# scheme.net
KiCad netlist of a schematic drawn in EAGLE
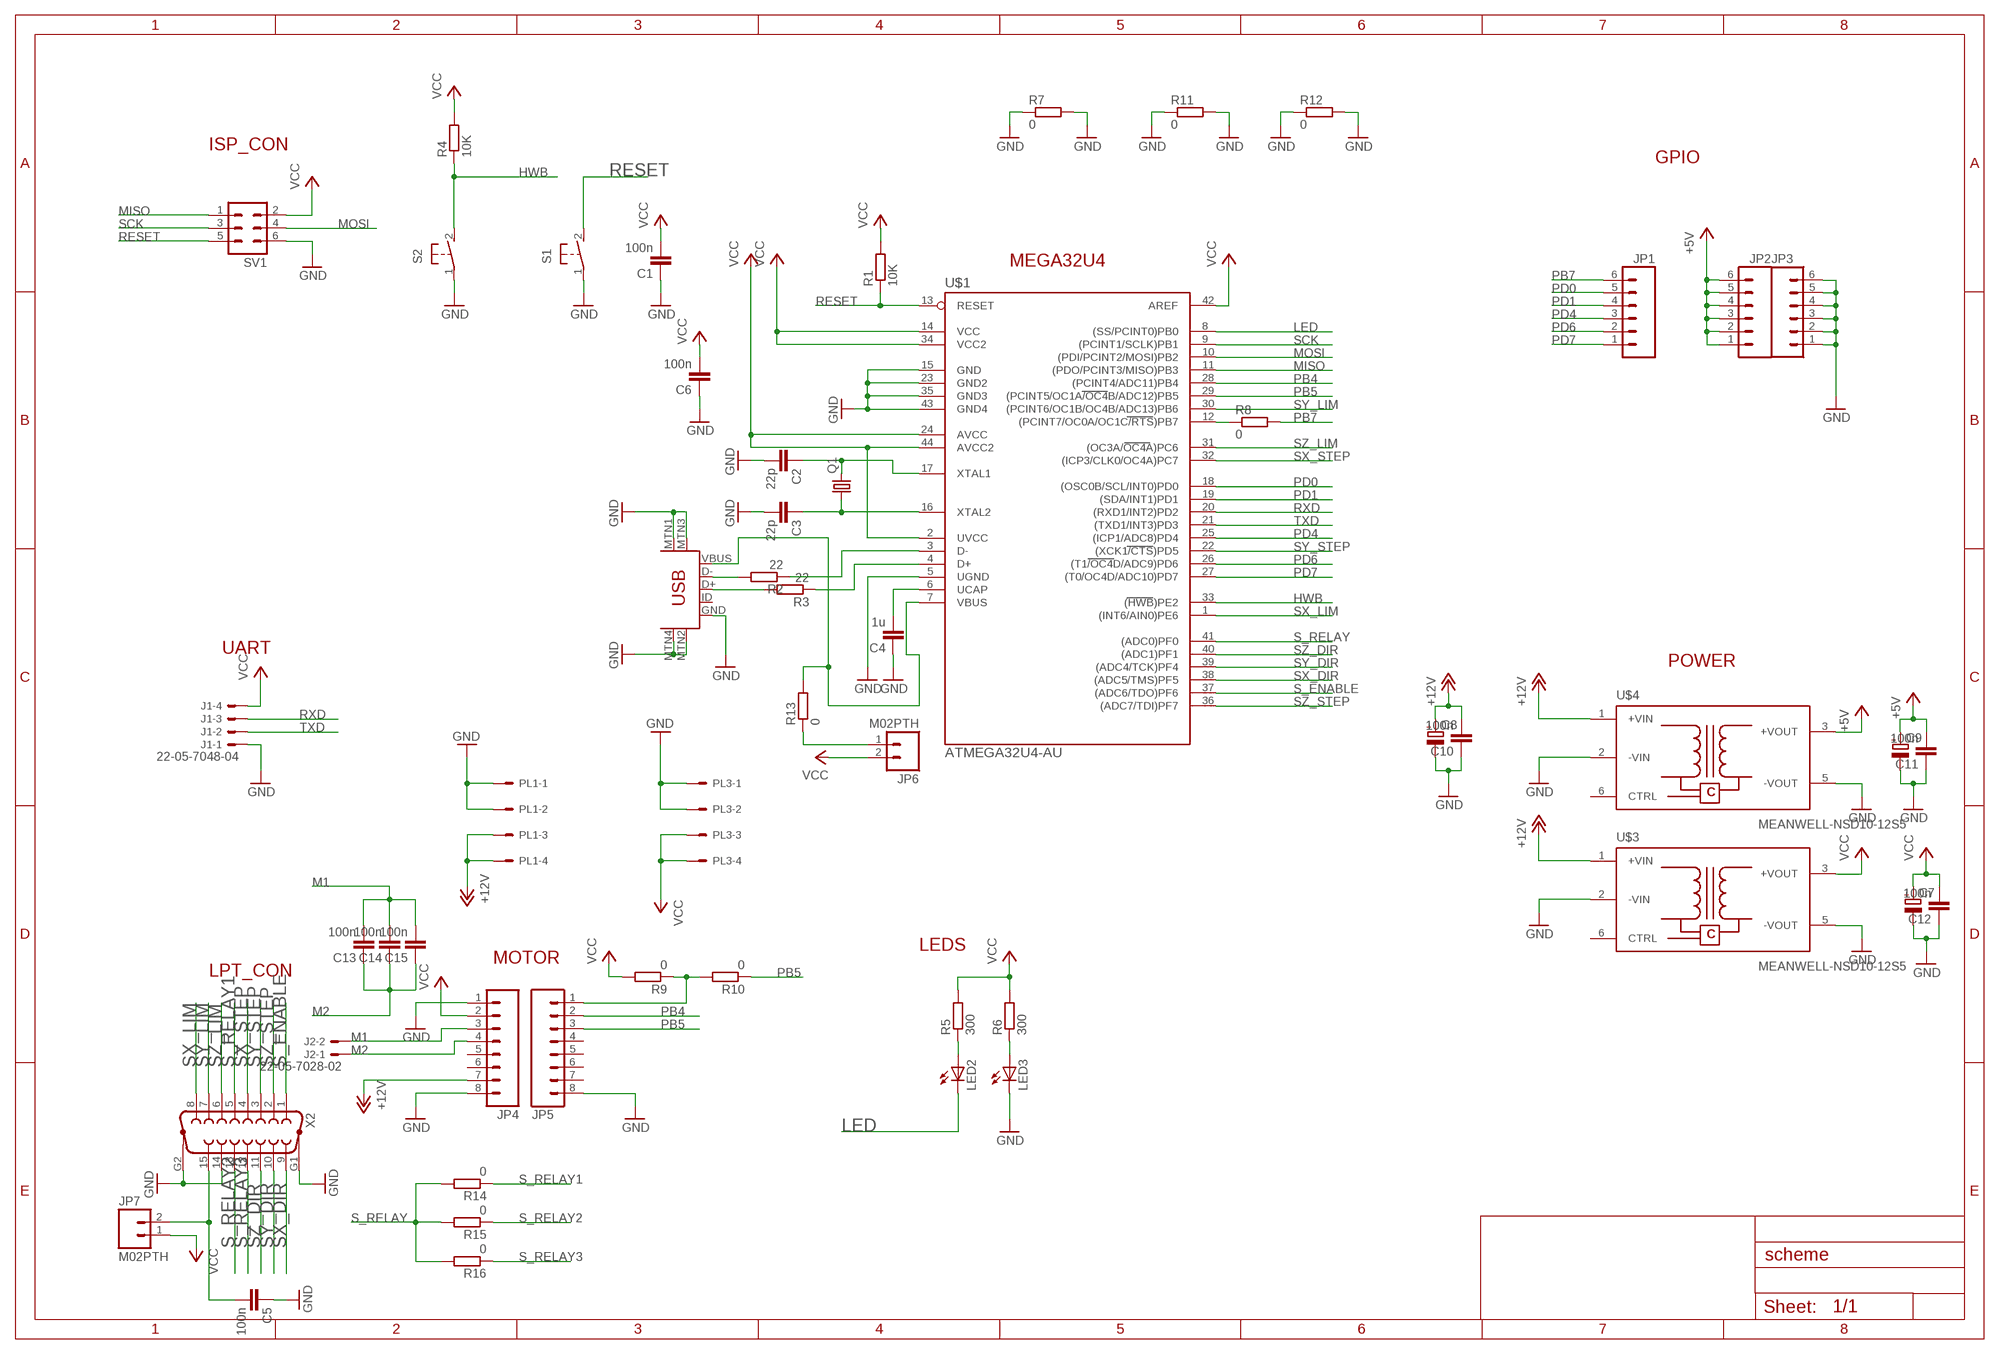
[diagram p0: schematic, sheet 1]

(export (version "E")
  (design (tool "Eeschema 10.0.6"))
  (components
    (comp (ref "C1")
      (value "100n")
      (footprint "eagle-import:C0805")
      (libsource (lib "eagle-import") (part "C-EUC0805"))
    )
    (comp (ref "C2")
      (value "22p")
      (footprint "eagle-import:C0805")
      (libsource (lib "eagle-import") (part "C-EUC0805"))
    )
    (comp (ref "C3")
      (value "22p")
      (footprint "eagle-import:C0805")
      (libsource (lib "eagle-import") (part "C-EUC0805"))
    )
    (comp (ref "C4")
      (value "1u")
      (footprint "eagle-import:C0805")
      (libsource (lib "eagle-import") (part "C-EUC0805"))
    )
    (comp (ref "C5")
      (value "100n")
      (footprint "eagle-import:C0805")
      (libsource (lib "eagle-import") (part "C-EUC0805"))
    )
    (comp (ref "C6")
      (value "100n")
      (footprint "eagle-import:C0805")
      (libsource (lib "eagle-import") (part "C-EUC0805"))
    )
    (comp (ref "C7")
      (value "CPOL-EUE2.5-6")
      (footprint "eagle-import:E2,5-6")
      (libsource (lib "eagle-import") (part "CPOL-EUE2.5-6"))
    )
    (comp (ref "C8")
      (value "CPOL-EUE2.5-6")
      (footprint "eagle-import:E2,5-6")
      (libsource (lib "eagle-import") (part "CPOL-EUE2.5-6"))
    )
    (comp (ref "C9")
      (value "CPOL-EUE2.5-6")
      (footprint "eagle-import:E2,5-6")
      (libsource (lib "eagle-import") (part "CPOL-EUE2.5-6"))
    )
    (comp (ref "C10")
      (value "100n")
      (footprint "eagle-import:C0805")
      (libsource (lib "eagle-import") (part "C-EUC0805"))
    )
    (comp (ref "C11")
      (value "100n")
      (footprint "eagle-import:C0805")
      (libsource (lib "eagle-import") (part "C-EUC0805"))
    )
    (comp (ref "C12")
      (value "100n")
      (footprint "eagle-import:C0805")
      (libsource (lib "eagle-import") (part "C-EUC0805"))
    )
    (comp (ref "C13")
      (value "100n")
      (footprint "eagle-import:C0805")
      (libsource (lib "eagle-import") (part "C-EUC0805"))
    )
    (comp (ref "C14")
      (value "100n")
      (footprint "eagle-import:C0805")
      (libsource (lib "eagle-import") (part "C-EUC0805"))
    )
    (comp (ref "C15")
      (value "100n")
      (footprint "eagle-import:C0805")
      (libsource (lib "eagle-import") (part "C-EUC0805"))
    )
    (comp (ref "J1")
      (value "22-05-7048-04")
      (footprint "eagle-import:7395-04")
      (libsource (lib "eagle-import") (part "22-?-0405-7048"))
    )
    (comp (ref "J2")
      (value "22-05-7028-02")
      (footprint "eagle-import:7395-02")
      (libsource (lib "eagle-import") (part "22-?-0205-7028"))
    )
    (comp (ref "JP1")
      (value "M06SIP")
      (footprint "eagle-import:1X06")
      (libsource (lib "eagle-import") (part "M06SIP"))
    )
    (comp (ref "JP2")
      (value "M06SIP")
      (footprint "eagle-import:1X06")
      (libsource (lib "eagle-import") (part "M06SIP"))
    )
    (comp (ref "JP3")
      (value "M06SIP")
      (footprint "eagle-import:1X06")
      (libsource (lib "eagle-import") (part "M06SIP"))
    )
    (comp (ref "JP4")
      (value "M081X08")
      (footprint "eagle-import:1X08")
      (libsource (lib "eagle-import") (part "M081X08"))
    )
    (comp (ref "JP5")
      (value "M081X08")
      (footprint "eagle-import:1X08")
      (libsource (lib "eagle-import") (part "M081X08"))
    )
    (comp (ref "JP6")
      (value "M02PTH")
      (footprint "eagle-import:1X02")
      (libsource (lib "eagle-import") (part "M02PTH"))
    )
    (comp (ref "JP7")
      (value "M02PTH")
      (footprint "eagle-import:1X02")
      (libsource (lib "eagle-import") (part "M02PTH"))
    )
    (comp (ref "LED2")
      (value "LED5MM")
      (footprint "eagle-import:LED5MM")
      (libsource (lib "eagle-import") (part "LED5MM"))
    )
    (comp (ref "LED3")
      (value "LED5MM")
      (footprint "eagle-import:LED5MM")
      (libsource (lib "eagle-import") (part "LED5MM"))
    )
    (comp (ref "PL1")
      (value "555X-4H")
      (footprint "eagle-import:5569-4")
      (libsource (lib "eagle-import") (part "555X-4H"))
    )
    (comp (ref "PL3")
      (value "555X-4H")
      (footprint "eagle-import:5569-4")
      (libsource (lib "eagle-import") (part "555X-4H"))
    )
    (comp (ref "Q1")
      (value "CRYSTALHC49S")
      (footprint "eagle-import:HC49_S")
      (libsource (lib "eagle-import") (part "CRYSTALHC49S"))
    )
    (comp (ref "R1")
      (value "10K")
      (footprint "eagle-import:R0805")
      (libsource (lib "eagle-import") (part "resistor_R-EU_R0805"))
    )
    (comp (ref "R2")
      (value "22")
      (footprint "eagle-import:R0805")
      (libsource (lib "eagle-import") (part "resistor_R-EU_R0805"))
    )
    (comp (ref "R3")
      (value "22")
      (footprint "eagle-import:R0805")
      (libsource (lib "eagle-import") (part "resistor_R-EU_R0805"))
    )
    (comp (ref "R4")
      (value "10K")
      (footprint "eagle-import:R0805")
      (libsource (lib "eagle-import") (part "resistor_R-EU_R0805"))
    )
    (comp (ref "R5")
      (value "300")
      (footprint "eagle-import:R0805")
      (libsource (lib "eagle-import") (part "resistor_R-EU_R0805"))
    )
    (comp (ref "R6")
      (value "300")
      (footprint "eagle-import:R0805")
      (libsource (lib "eagle-import") (part "resistor_R-EU_R0805"))
    )
    (comp (ref "R7")
      (value "0")
      (footprint "eagle-import:R1206")
      (libsource (lib "eagle-import") (part "R-EU_R1206"))
    )
    (comp (ref "R8")
      (value "0")
      (footprint "eagle-import:R1206")
      (libsource (lib "eagle-import") (part "R-EU_R1206"))
    )
    (comp (ref "R9")
      (value "0")
      (footprint "eagle-import:R0805")
      (libsource (lib "eagle-import") (part "resistor_R-EU_R0805"))
    )
    (comp (ref "R10")
      (value "0")
      (footprint "eagle-import:R0805")
      (libsource (lib "eagle-import") (part "resistor_R-EU_R0805"))
    )
    (comp (ref "R11")
      (value "0")
      (footprint "eagle-import:R1206")
      (libsource (lib "eagle-import") (part "R-EU_R1206"))
    )
    (comp (ref "R12")
      (value "0")
      (footprint "eagle-import:R1206")
      (libsource (lib "eagle-import") (part "R-EU_R1206"))
    )
    (comp (ref "R13")
      (value "0")
      (footprint "eagle-import:R1206")
      (libsource (lib "eagle-import") (part "R-EU_R1206"))
    )
    (comp (ref "R14")
      (value "0")
      (footprint "eagle-import:R0805")
      (libsource (lib "eagle-import") (part "resistor_R-EU_R0805"))
    )
    (comp (ref "R15")
      (value "0")
      (footprint "eagle-import:R0805")
      (libsource (lib "eagle-import") (part "resistor_R-EU_R0805"))
    )
    (comp (ref "R16")
      (value "0")
      (footprint "eagle-import:R0805")
      (libsource (lib "eagle-import") (part "resistor_R-EU_R0805"))
    )
    (comp (ref "S1")
      (value "31-XX")
      (footprint "eagle-import:B3F-31XX")
      (fields (field (name "MPN") "B3F-3100"))
      (libsource (lib "eagle-import") (part "31-XX"))
    )
    (comp (ref "S2")
      (value "31-XX")
      (footprint "eagle-import:B3F-31XX")
      (fields (field (name "MPN") "B3F-3100"))
      (libsource (lib "eagle-import") (part "31-XX"))
    )
    (comp (ref "SV1")
      (value "ML6L")
      (footprint "eagle-import:ML6L")
      (libsource (lib "eagle-import") (part "ML6L"))
    )
    (comp (ref "U$1")
      (value "ATMEGA32U4-AU")
      (footprint "eagle-import:TQFP44")
      (libsource (lib "eagle-import") (part "ATMEGA32U4-AU"))
    )
    (comp (ref "U$2")
      (value "USB-MINIB-5PIN")
      (footprint "eagle-import:USB-MINIB")
      (libsource (lib "eagle-import") (part "USB-MINIB-5PIN"))
    )
    (comp (ref "U$3")
      (value "MEANWELL-NSD10-12S5")
      (footprint "eagle-import:POWER6-10W")
      (libsource (lib "eagle-import") (part "MEANWELL-NSD10-12S5"))
    )
    (comp (ref "U$4")
      (value "MEANWELL-NSD10-12S5")
      (footprint "eagle-import:POWER6-10W")
      (libsource (lib "eagle-import") (part "MEANWELL-NSD10-12S5"))
    )
    (comp (ref "X2")
      (value "F15HP")
      (footprint "eagle-import:F15HP")
      (libsource (lib "eagle-import") (part "F15HP"))
    )
  )
  (nets
    (net (code "1") (name "+5V") (class "Default")
      (node (ref "C11") (pin "2") (pinfunction "2_2") (pintype "passive"))
      (node (ref "C9") (pin "+") (pinfunction "+_+") (pintype "passive"))
      (node (ref "JP2") (pin "1") (pinfunction "1_1") (pintype "passive"))
      (node (ref "JP2") (pin "2") (pinfunction "2_2") (pintype "passive"))
      (node (ref "JP2") (pin "3") (pinfunction "3_3") (pintype "passive"))
      (node (ref "JP2") (pin "4") (pinfunction "4_4") (pintype "passive"))
      (node (ref "JP2") (pin "5") (pinfunction "5_5") (pintype "passive"))
      (node (ref "JP2") (pin "6") (pinfunction "6_6") (pintype "passive"))
      (node (ref "U$4") (pin "3") (pinfunction "+VOUT_3") (pintype "output"))
    )
    (net (code "2") (name "+12V") (class "Default")
      (node (ref "C10") (pin "2") (pinfunction "2_2") (pintype "passive"))
      (node (ref "C8") (pin "+") (pinfunction "+_+") (pintype "passive"))
      (node (ref "JP4") (pin "7") (pinfunction "7_7") (pintype "passive"))
      (node (ref "PL1") (pin "3") (pinfunction "S_3") (pintype "passive"))
      (node (ref "PL1") (pin "4") (pinfunction "S_4") (pintype "passive"))
      (node (ref "U$3") (pin "1") (pinfunction "+VIN_1") (pintype "input"))
      (node (ref "U$4") (pin "1") (pinfunction "+VIN_1") (pintype "input"))
    )
    (net (code "3") (name "/HWB") (class "Default")
      (node (ref "R4") (pin "1") (pinfunction "1_1") (pintype "passive"))
      (node (ref "S2") (pin "2") (pinfunction "S_2") (pintype "passive"))
      (node (ref "U$1") (pin "33") (pinfunction "(HWB)PE2_33") (pintype "bidirectional"))
    )
    (net (code "4") (name "/LED") (class "Default")
      (node (ref "LED2") (pin "K") (pinfunction "C_K") (pintype "passive"))
      (node (ref "U$1") (pin "8") (pinfunction "(SS/PCINT0)PB0_8") (pintype "bidirectional"))
    )
    (net (code "5") (name "/M1") (class "Default")
      (node (ref "C13") (pin "2") (pinfunction "2_2") (pintype "passive"))
      (node (ref "C14") (pin "2") (pinfunction "2_2") (pintype "passive"))
      (node (ref "C15") (pin "2") (pinfunction "2_2") (pintype "passive"))
      (node (ref "J2") (pin "2") (pinfunction "S_2") (pintype "passive"))
      (node (ref "JP4") (pin "3") (pinfunction "3_3") (pintype "passive"))
    )
    (net (code "6") (name "/M2") (class "Default")
      (node (ref "C13") (pin "1") (pinfunction "1_1") (pintype "passive"))
      (node (ref "C14") (pin "1") (pinfunction "1_1") (pintype "passive"))
      (node (ref "C15") (pin "1") (pinfunction "1_1") (pintype "passive"))
      (node (ref "J2") (pin "1") (pinfunction "S_1") (pintype "passive"))
      (node (ref "JP4") (pin "4") (pinfunction "4_4") (pintype "passive"))
    )
    (net (code "7") (name "/MISO") (class "Default")
      (node (ref "SV1") (pin "1") (pinfunction "1_1") (pintype "passive"))
      (node (ref "U$1") (pin "11") (pinfunction "(PDO/PCINT3/MISO)PB3_11") (pintype "bidirectional"))
    )
    (net (code "8") (name "/MOSI") (class "Default")
      (node (ref "SV1") (pin "4") (pinfunction "4_4") (pintype "passive"))
      (node (ref "U$1") (pin "10") (pinfunction "(PDI/PCINT2/MOSI)PB2_10") (pintype "bidirectional"))
    )
    (net (code "9") (name "/PB4") (class "Default")
      (node (ref "JP5") (pin "2") (pinfunction "2_2") (pintype "passive"))
      (node (ref "U$1") (pin "28") (pinfunction "(PCINT4/ADC11)PB4_28") (pintype "bidirectional"))
    )
    (net (code "10") (name "/PB5") (class "Default")
      (node (ref "JP5") (pin "3") (pinfunction "3_3") (pintype "passive"))
      (node (ref "R10") (pin "1") (pinfunction "1_1") (pintype "passive"))
      (node (ref "U$1") (pin "29") (pinfunction "(PCINT5/OC1A/OC4B/ADC12)PB5_29") (pintype "bidirectional"))
    )
    (net (code "11") (name "/PB7") (class "Default")
      (node (ref "JP1") (pin "6") (pinfunction "6_6") (pintype "passive"))
      (node (ref "R8") (pin "2") (pinfunction "2_2") (pintype "passive"))
    )
    (net (code "12") (name "/PD0") (class "Default")
      (node (ref "JP1") (pin "5") (pinfunction "5_5") (pintype "passive"))
      (node (ref "U$1") (pin "18") (pinfunction "(OSC0B/SCL/INT0)PD0_18") (pintype "bidirectional"))
    )
    (net (code "13") (name "/PD1") (class "Default")
      (node (ref "JP1") (pin "4") (pinfunction "4_4") (pintype "passive"))
      (node (ref "U$1") (pin "19") (pinfunction "(SDA/INT1)PD1_19") (pintype "bidirectional"))
    )
    (net (code "14") (name "/PD4") (class "Default")
      (node (ref "JP1") (pin "3") (pinfunction "3_3") (pintype "passive"))
      (node (ref "U$1") (pin "25") (pinfunction "(ICP1/ADC8)PD4_25") (pintype "bidirectional"))
    )
    (net (code "15") (name "/PD6") (class "Default")
      (node (ref "JP1") (pin "2") (pinfunction "2_2") (pintype "passive"))
      (node (ref "U$1") (pin "26") (pinfunction "(T1/OC4D/ADC9)PD6_26") (pintype "bidirectional"))
    )
    (net (code "16") (name "/PD7") (class "Default")
      (node (ref "JP1") (pin "1") (pinfunction "1_1") (pintype "passive"))
      (node (ref "U$1") (pin "27") (pinfunction "(T0/OC4D/ADC10)PD7_27") (pintype "bidirectional"))
    )
    (net (code "17") (name "/RESET") (class "Default")
      (node (ref "R1") (pin "1") (pinfunction "1_1") (pintype "passive"))
      (node (ref "S1") (pin "2") (pinfunction "S_2") (pintype "passive"))
      (node (ref "SV1") (pin "5") (pinfunction "5_5") (pintype "passive"))
      (node (ref "U$1") (pin "13") (pinfunction "RESET_13") (pintype "bidirectional"))
    )
    (net (code "18") (name "/RXD") (class "Default")
      (node (ref "J1") (pin "3") (pinfunction "S_3") (pintype "passive"))
      (node (ref "U$1") (pin "20") (pinfunction "(RXD1/INT2)PD2_20") (pintype "bidirectional"))
    )
    (net (code "19") (name "/SCK") (class "Default")
      (node (ref "SV1") (pin "3") (pinfunction "3_3") (pintype "passive"))
      (node (ref "U$1") (pin "9") (pinfunction "(PCINT1/SCLK)PB1_9") (pintype "bidirectional"))
    )
    (net (code "20") (name "/SX_DIR") (class "Default")
      (node (ref "U$1") (pin "38") (pinfunction "(ADC5/TMS)PF5_38") (pintype "bidirectional"))
      (node (ref "X2") (pin "9") (pinfunction "9_9") (pintype "passive"))
    )
    (net (code "21") (name "/SX_LIM") (class "Default")
      (node (ref "U$1") (pin "1") (pinfunction "(INT6/AIN0)PE6_1") (pintype "bidirectional"))
      (node (ref "X2") (pin "8") (pinfunction "8_8") (pintype "passive"))
    )
    (net (code "22") (name "/SX_STEP") (class "Default")
      (node (ref "U$1") (pin "32") (pinfunction "(ICP3/CLK0/OC4A)PC7_32") (pintype "bidirectional"))
      (node (ref "X2") (pin "4") (pinfunction "4_4") (pintype "passive"))
    )
    (net (code "23") (name "/SY_DIR") (class "Default")
      (node (ref "U$1") (pin "39") (pinfunction "(ADC4/TCK)PF4_39") (pintype "bidirectional"))
      (node (ref "X2") (pin "10") (pinfunction "10_10") (pintype "passive"))
    )
    (net (code "24") (name "/SY_LIM") (class "Default")
      (node (ref "U$1") (pin "30") (pinfunction "(PCINT6/OC1B/OC4B/ADC13)PB6_30") (pintype "bidirectional"))
      (node (ref "X2") (pin "7") (pinfunction "7_7") (pintype "passive"))
    )
    (net (code "25") (name "/SY_STEP") (class "Default")
      (node (ref "U$1") (pin "22") (pinfunction "(XCK1/CTS)PD5_22") (pintype "bidirectional"))
      (node (ref "X2") (pin "3") (pinfunction "3_3") (pintype "passive"))
    )
    (net (code "26") (name "/SZ_DIR") (class "Default")
      (node (ref "U$1") (pin "40") (pinfunction "(ADC1)PF1_40") (pintype "bidirectional"))
      (node (ref "X2") (pin "11") (pinfunction "11_11") (pintype "passive"))
    )
    (net (code "27") (name "/SZ_LIM") (class "Default")
      (node (ref "U$1") (pin "31") (pinfunction "(OC3A/OC4A)PC6_31") (pintype "bidirectional"))
      (node (ref "X2") (pin "6") (pinfunction "6_6") (pintype "passive"))
    )
    (net (code "28") (name "/SZ_STEP") (class "Default")
      (node (ref "U$1") (pin "36") (pinfunction "(ADC7/TDI)PF7_36") (pintype "bidirectional"))
      (node (ref "X2") (pin "2") (pinfunction "2_2") (pintype "passive"))
    )
    (net (code "29") (name "/S_ENABLE") (class "Default")
      (node (ref "U$1") (pin "37") (pinfunction "(ADC6/TDO)PF6_37") (pintype "bidirectional"))
      (node (ref "X2") (pin "1") (pinfunction "1_1") (pintype "passive"))
    )
    (net (code "30") (name "/S_RELAY") (class "Default")
      (node (ref "R14") (pin "2") (pinfunction "2_2") (pintype "passive"))
      (node (ref "R15") (pin "2") (pinfunction "2_2") (pintype "passive"))
      (node (ref "R16") (pin "2") (pinfunction "2_2") (pintype "passive"))
      (node (ref "U$1") (pin "41") (pinfunction "(ADC0)PF0_41") (pintype "bidirectional"))
    )
    (net (code "31") (name "/S_RELAY1") (class "Default")
      (node (ref "R14") (pin "1") (pinfunction "1_1") (pintype "passive"))
      (node (ref "X2") (pin "5") (pinfunction "5_5") (pintype "passive"))
    )
    (net (code "32") (name "/S_RELAY2") (class "Default")
      (node (ref "R15") (pin "1") (pinfunction "1_1") (pintype "passive"))
      (node (ref "X2") (pin "13") (pinfunction "13_13") (pintype "passive"))
    )
    (net (code "33") (name "/S_RELAY3") (class "Default")
      (node (ref "R16") (pin "1") (pinfunction "1_1") (pintype "passive"))
      (node (ref "X2") (pin "12") (pinfunction "12_12") (pintype "passive"))
    )
    (net (code "34") (name "/TXD") (class "Default")
      (node (ref "J1") (pin "2") (pinfunction "S_2") (pintype "passive"))
      (node (ref "U$1") (pin "21") (pinfunction "(TXD1/INT3)PD3_21") (pintype "bidirectional"))
    )
    (net (code "35") (name "GND") (class "Default")
      (node (ref "C1") (pin "1") (pinfunction "1_1") (pintype "passive"))
      (node (ref "C10") (pin "1") (pinfunction "1_1") (pintype "passive"))
      (node (ref "C11") (pin "1") (pinfunction "1_1") (pintype "passive"))
      (node (ref "C12") (pin "1") (pinfunction "1_1") (pintype "passive"))
      (node (ref "C2") (pin "2") (pinfunction "2_2") (pintype "passive"))
      (node (ref "C3") (pin "2") (pinfunction "2_2") (pintype "passive"))
      (node (ref "C4") (pin "1") (pinfunction "1_1") (pintype "passive"))
      (node (ref "C5") (pin "1") (pinfunction "1_1") (pintype "passive"))
      (node (ref "C6") (pin "1") (pinfunction "1_1") (pintype "passive"))
      (node (ref "C7") (pin "-") (pinfunction "-_-") (pintype "passive"))
      (node (ref "C8") (pin "-") (pinfunction "-_-") (pintype "passive"))
      (node (ref "C9") (pin "-") (pinfunction "-_-") (pintype "passive"))
      (node (ref "J1") (pin "1") (pinfunction "S_1") (pintype "passive"))
      (node (ref "JP3") (pin "1") (pinfunction "1_1") (pintype "passive"))
      (node (ref "JP3") (pin "2") (pinfunction "2_2") (pintype "passive"))
      (node (ref "JP3") (pin "3") (pinfunction "3_3") (pintype "passive"))
      (node (ref "JP3") (pin "4") (pinfunction "4_4") (pintype "passive"))
      (node (ref "JP3") (pin "5") (pinfunction "5_5") (pintype "passive"))
      (node (ref "JP3") (pin "6") (pinfunction "6_6") (pintype "passive"))
      (node (ref "JP4") (pin "1") (pinfunction "1_1") (pintype "passive"))
      (node (ref "JP4") (pin "8") (pinfunction "8_8") (pintype "passive"))
      (node (ref "JP5") (pin "8") (pinfunction "8_8") (pintype "passive"))
      (node (ref "LED3") (pin "K") (pinfunction "C_K") (pintype "passive"))
      (node (ref "PL1") (pin "1") (pinfunction "S_1") (pintype "passive"))
      (node (ref "PL1") (pin "2") (pinfunction "S_2") (pintype "passive"))
      (node (ref "PL3") (pin "1") (pinfunction "S_1") (pintype "passive"))
      (node (ref "PL3") (pin "2") (pinfunction "S_2") (pintype "passive"))
      (node (ref "R11") (pin "1") (pinfunction "1_1") (pintype "passive"))
      (node (ref "R11") (pin "2") (pinfunction "2_2") (pintype "passive"))
      (node (ref "R12") (pin "1") (pinfunction "1_1") (pintype "passive"))
      (node (ref "R12") (pin "2") (pinfunction "2_2") (pintype "passive"))
      (node (ref "R7") (pin "1") (pinfunction "1_1") (pintype "passive"))
      (node (ref "R7") (pin "2") (pinfunction "2_2") (pintype "passive"))
      (node (ref "S1") (pin "1") (pinfunction "P_1") (pintype "passive"))
      (node (ref "S2") (pin "1") (pinfunction "P_1") (pintype "passive"))
      (node (ref "SV1") (pin "6") (pinfunction "6_6") (pintype "passive"))
      (node (ref "U$1") (pin "15") (pinfunction "GND_15") (pintype "bidirectional"))
      (node (ref "U$1") (pin "23") (pinfunction "GND2_23") (pintype "bidirectional"))
      (node (ref "U$1") (pin "35") (pinfunction "GND3_35") (pintype "bidirectional"))
      (node (ref "U$1") (pin "43") (pinfunction "GND4_43") (pintype "bidirectional"))
      (node (ref "U$1") (pin "5") (pinfunction "UGND_5") (pintype "bidirectional"))
      (node (ref "U$2") (pin "GND") (pinfunction "GND_GND") (pintype "bidirectional"))
      (node (ref "U$2") (pin "MTN1") (pinfunction "MTN2_MTN1") (pintype "bidirectional"))
      (node (ref "U$2") (pin "MTN2") (pinfunction "MTN3_MTN2") (pintype "bidirectional"))
      (node (ref "U$2") (pin "MTN3") (pinfunction "MTN1_MTN3") (pintype "bidirectional"))
      (node (ref "U$2") (pin "MTN4") (pinfunction "MTN4_MTN4") (pintype "bidirectional"))
      (node (ref "U$3") (pin "2") (pinfunction "-VIN_2") (pintype "input"))
      (node (ref "U$3") (pin "5") (pinfunction "-VOUT_5") (pintype "output"))
      (node (ref "U$4") (pin "2") (pinfunction "-VIN_2") (pintype "input"))
      (node (ref "U$4") (pin "5") (pinfunction "-VOUT_5") (pintype "output"))
      (node (ref "X2") (pin "14") (pinfunction "14_14") (pintype "passive"))
      (node (ref "X2") (pin "G1") (pinfunction "G1_G1") (pintype "passive"))
      (node (ref "X2") (pin "G2") (pinfunction "G2_G2") (pintype "passive"))
    )
    (net (code "36") (name "Net-(C5-Pad2)") (class "Default")
      (node (ref "C5") (pin "2") (pinfunction "2_2") (pintype "passive"))
      (node (ref "JP7") (pin "2") (pinfunction "2_2") (pintype "passive"))
      (node (ref "X2") (pin "15") (pinfunction "15_15") (pintype "passive"))
    )
    (net (code "37") (name "Net-(JP5-Pad1)") (class "Default")
      (node (ref "JP5") (pin "1") (pinfunction "1_1") (pintype "passive"))
      (node (ref "R10") (pin "2") (pinfunction "2_2") (pintype "passive"))
      (node (ref "R9") (pin "1") (pinfunction "1_1") (pintype "passive"))
    )
    (net (code "38") (name "Net-(JP6-Pad1)") (class "Default")
      (node (ref "JP6") (pin "1") (pinfunction "1_1") (pintype "passive"))
      (node (ref "R13") (pin "1") (pinfunction "1_1") (pintype "passive"))
    )
    (net (code "39") (name "Net-(LED2-PadA)") (class "Default")
      (node (ref "LED2") (pin "A") (pinfunction "A_A") (pintype "passive"))
      (node (ref "R5") (pin "1") (pinfunction "1_1") (pintype "passive"))
    )
    (net (code "40") (name "Net-(LED3-PadA)") (class "Default")
      (node (ref "LED3") (pin "A") (pinfunction "A_A") (pintype "passive"))
      (node (ref "R6") (pin "1") (pinfunction "1_1") (pintype "passive"))
    )
    (net (code "41") (name "Net-(R2-Pad2)") (class "Default")
      (node (ref "R2") (pin "2") (pinfunction "2_2") (pintype "passive"))
      (node (ref "U$2") (pin "D-") (pinfunction "D-_D-") (pintype "bidirectional"))
    )
    (net (code "42") (name "Net-(R3-Pad2)") (class "Default")
      (node (ref "R3") (pin "2") (pinfunction "2_2") (pintype "passive"))
      (node (ref "U$2") (pin "D+") (pinfunction "D+_D+") (pintype "bidirectional"))
    )
    (net (code "43") (name "Net-(U$1-(PCINT7{slash}OC0A{slash}OC1C{slash}RTS)PB7)") (class "Default")
      (node (ref "R8") (pin "1") (pinfunction "1_1") (pintype "passive"))
      (node (ref "U$1") (pin "12") (pinfunction "(PCINT7/OC0A/OC1C/RTS)PB7_12") (pintype "bidirectional"))
    )
    (net (code "44") (name "Net-(U$1-D+)") (class "Default")
      (node (ref "R3") (pin "1") (pinfunction "1_1") (pintype "passive"))
      (node (ref "U$1") (pin "4") (pinfunction "D+_4") (pintype "bidirectional"))
    )
    (net (code "45") (name "Net-(U$1-D-)") (class "Default")
      (node (ref "R2") (pin "1") (pinfunction "1_1") (pintype "passive"))
      (node (ref "U$1") (pin "3") (pinfunction "D-_3") (pintype "bidirectional"))
    )
    (net (code "46") (name "Net-(U$1-UCAP)") (class "Default")
      (node (ref "C4") (pin "2") (pinfunction "2_2") (pintype "passive"))
      (node (ref "U$1") (pin "6") (pinfunction "UCAP_6") (pintype "bidirectional"))
    )
    (net (code "47") (name "Net-(U$1-VBUS)") (class "Default")
      (node (ref "R13") (pin "2") (pinfunction "2_2") (pintype "passive"))
      (node (ref "U$1") (pin "7") (pinfunction "VBUS_7") (pintype "bidirectional"))
      (node (ref "U$2") (pin "VBUS") (pinfunction "VBUS_VBUS") (pintype "bidirectional"))
    )
    (net (code "48") (name "Net-(U$1-XTAL1)") (class "Default")
      (node (ref "C2") (pin "1") (pinfunction "1_1") (pintype "passive"))
      (node (ref "Q1") (pin "2") (pinfunction "2_2") (pintype "passive"))
      (node (ref "U$1") (pin "17") (pinfunction "XTAL1_17") (pintype "bidirectional"))
    )
    (net (code "49") (name "Net-(U$1-XTAL2)") (class "Default")
      (node (ref "C3") (pin "1") (pinfunction "1_1") (pintype "passive"))
      (node (ref "Q1") (pin "1") (pinfunction "1_1") (pintype "passive"))
      (node (ref "U$1") (pin "16") (pinfunction "XTAL2_16") (pintype "bidirectional"))
    )
    (net (code "50") (name "VCC") (class "Default")
      (node (ref "C1") (pin "2") (pinfunction "2_2") (pintype "passive"))
      (node (ref "C12") (pin "2") (pinfunction "2_2") (pintype "passive"))
      (node (ref "C6") (pin "2") (pinfunction "2_2") (pintype "passive"))
      (node (ref "C7") (pin "+") (pinfunction "+_+") (pintype "passive"))
      (node (ref "J1") (pin "4") (pinfunction "S_4") (pintype "passive"))
      (node (ref "JP4") (pin "2") (pinfunction "2_2") (pintype "passive"))
      (node (ref "JP6") (pin "2") (pinfunction "2_2") (pintype "passive"))
      (node (ref "JP7") (pin "1") (pinfunction "1_1") (pintype "passive"))
      (node (ref "PL3") (pin "3") (pinfunction "S_3") (pintype "passive"))
      (node (ref "PL3") (pin "4") (pinfunction "S_4") (pintype "passive"))
      (node (ref "R1") (pin "2") (pinfunction "2_2") (pintype "passive"))
      (node (ref "R4") (pin "2") (pinfunction "2_2") (pintype "passive"))
      (node (ref "R5") (pin "2") (pinfunction "2_2") (pintype "passive"))
      (node (ref "R6") (pin "2") (pinfunction "2_2") (pintype "passive"))
      (node (ref "R9") (pin "2") (pinfunction "2_2") (pintype "passive"))
      (node (ref "SV1") (pin "2") (pinfunction "2_2") (pintype "passive"))
      (node (ref "U$1") (pin "14") (pinfunction "VCC_14") (pintype "bidirectional"))
      (node (ref "U$1") (pin "2") (pinfunction "UVCC_2") (pintype "bidirectional"))
      (node (ref "U$1") (pin "24") (pinfunction "AVCC_24") (pintype "bidirectional"))
      (node (ref "U$1") (pin "34") (pinfunction "VCC2_34") (pintype "bidirectional"))
      (node (ref "U$1") (pin "42") (pinfunction "AREF_42") (pintype "bidirectional"))
      (node (ref "U$1") (pin "44") (pinfunction "AVCC2_44") (pintype "bidirectional"))
      (node (ref "U$3") (pin "3") (pinfunction "+VOUT_3") (pintype "output"))
    )
    (net (code "51") (name "unconnected-(JP4-Pad5)") (class "Default")
      (node (ref "JP4") (pin "5") (pinfunction "5_5") (pintype "passive"))
    )
    (net (code "52") (name "unconnected-(JP4-Pad6)") (class "Default")
      (node (ref "JP4") (pin "6") (pinfunction "6_6") (pintype "passive"))
    )
    (net (code "53") (name "unconnected-(JP5-Pad4)") (class "Default")
      (node (ref "JP5") (pin "4") (pinfunction "4_4") (pintype "passive"))
    )
    (net (code "54") (name "unconnected-(JP5-Pad5)") (class "Default")
      (node (ref "JP5") (pin "5") (pinfunction "5_5") (pintype "passive"))
    )
    (net (code "55") (name "unconnected-(JP5-Pad6)") (class "Default")
      (node (ref "JP5") (pin "6") (pinfunction "6_6") (pintype "passive"))
    )
    (net (code "56") (name "unconnected-(JP5-Pad7)") (class "Default")
      (node (ref "JP5") (pin "7") (pinfunction "7_7") (pintype "passive"))
    )
    (net (code "57") (name "unconnected-(U$2-PadID)") (class "Default")
      (node (ref "U$2") (pin "ID") (pinfunction "ID_ID") (pintype "bidirectional"))
    )
    (net (code "58") (name "unconnected-(U$3-CTRL-Pad6)") (class "Default")
      (node (ref "U$3") (pin "6") (pinfunction "CTRL_6") (pintype "bidirectional"))
    )
    (net (code "59") (name "unconnected-(U$4-CTRL-Pad6)") (class "Default")
      (node (ref "U$4") (pin "6") (pinfunction "CTRL_6") (pintype "bidirectional"))
    )
  )
)
